# Display.net
KiCad netlist of a schematic drawn in EAGLE
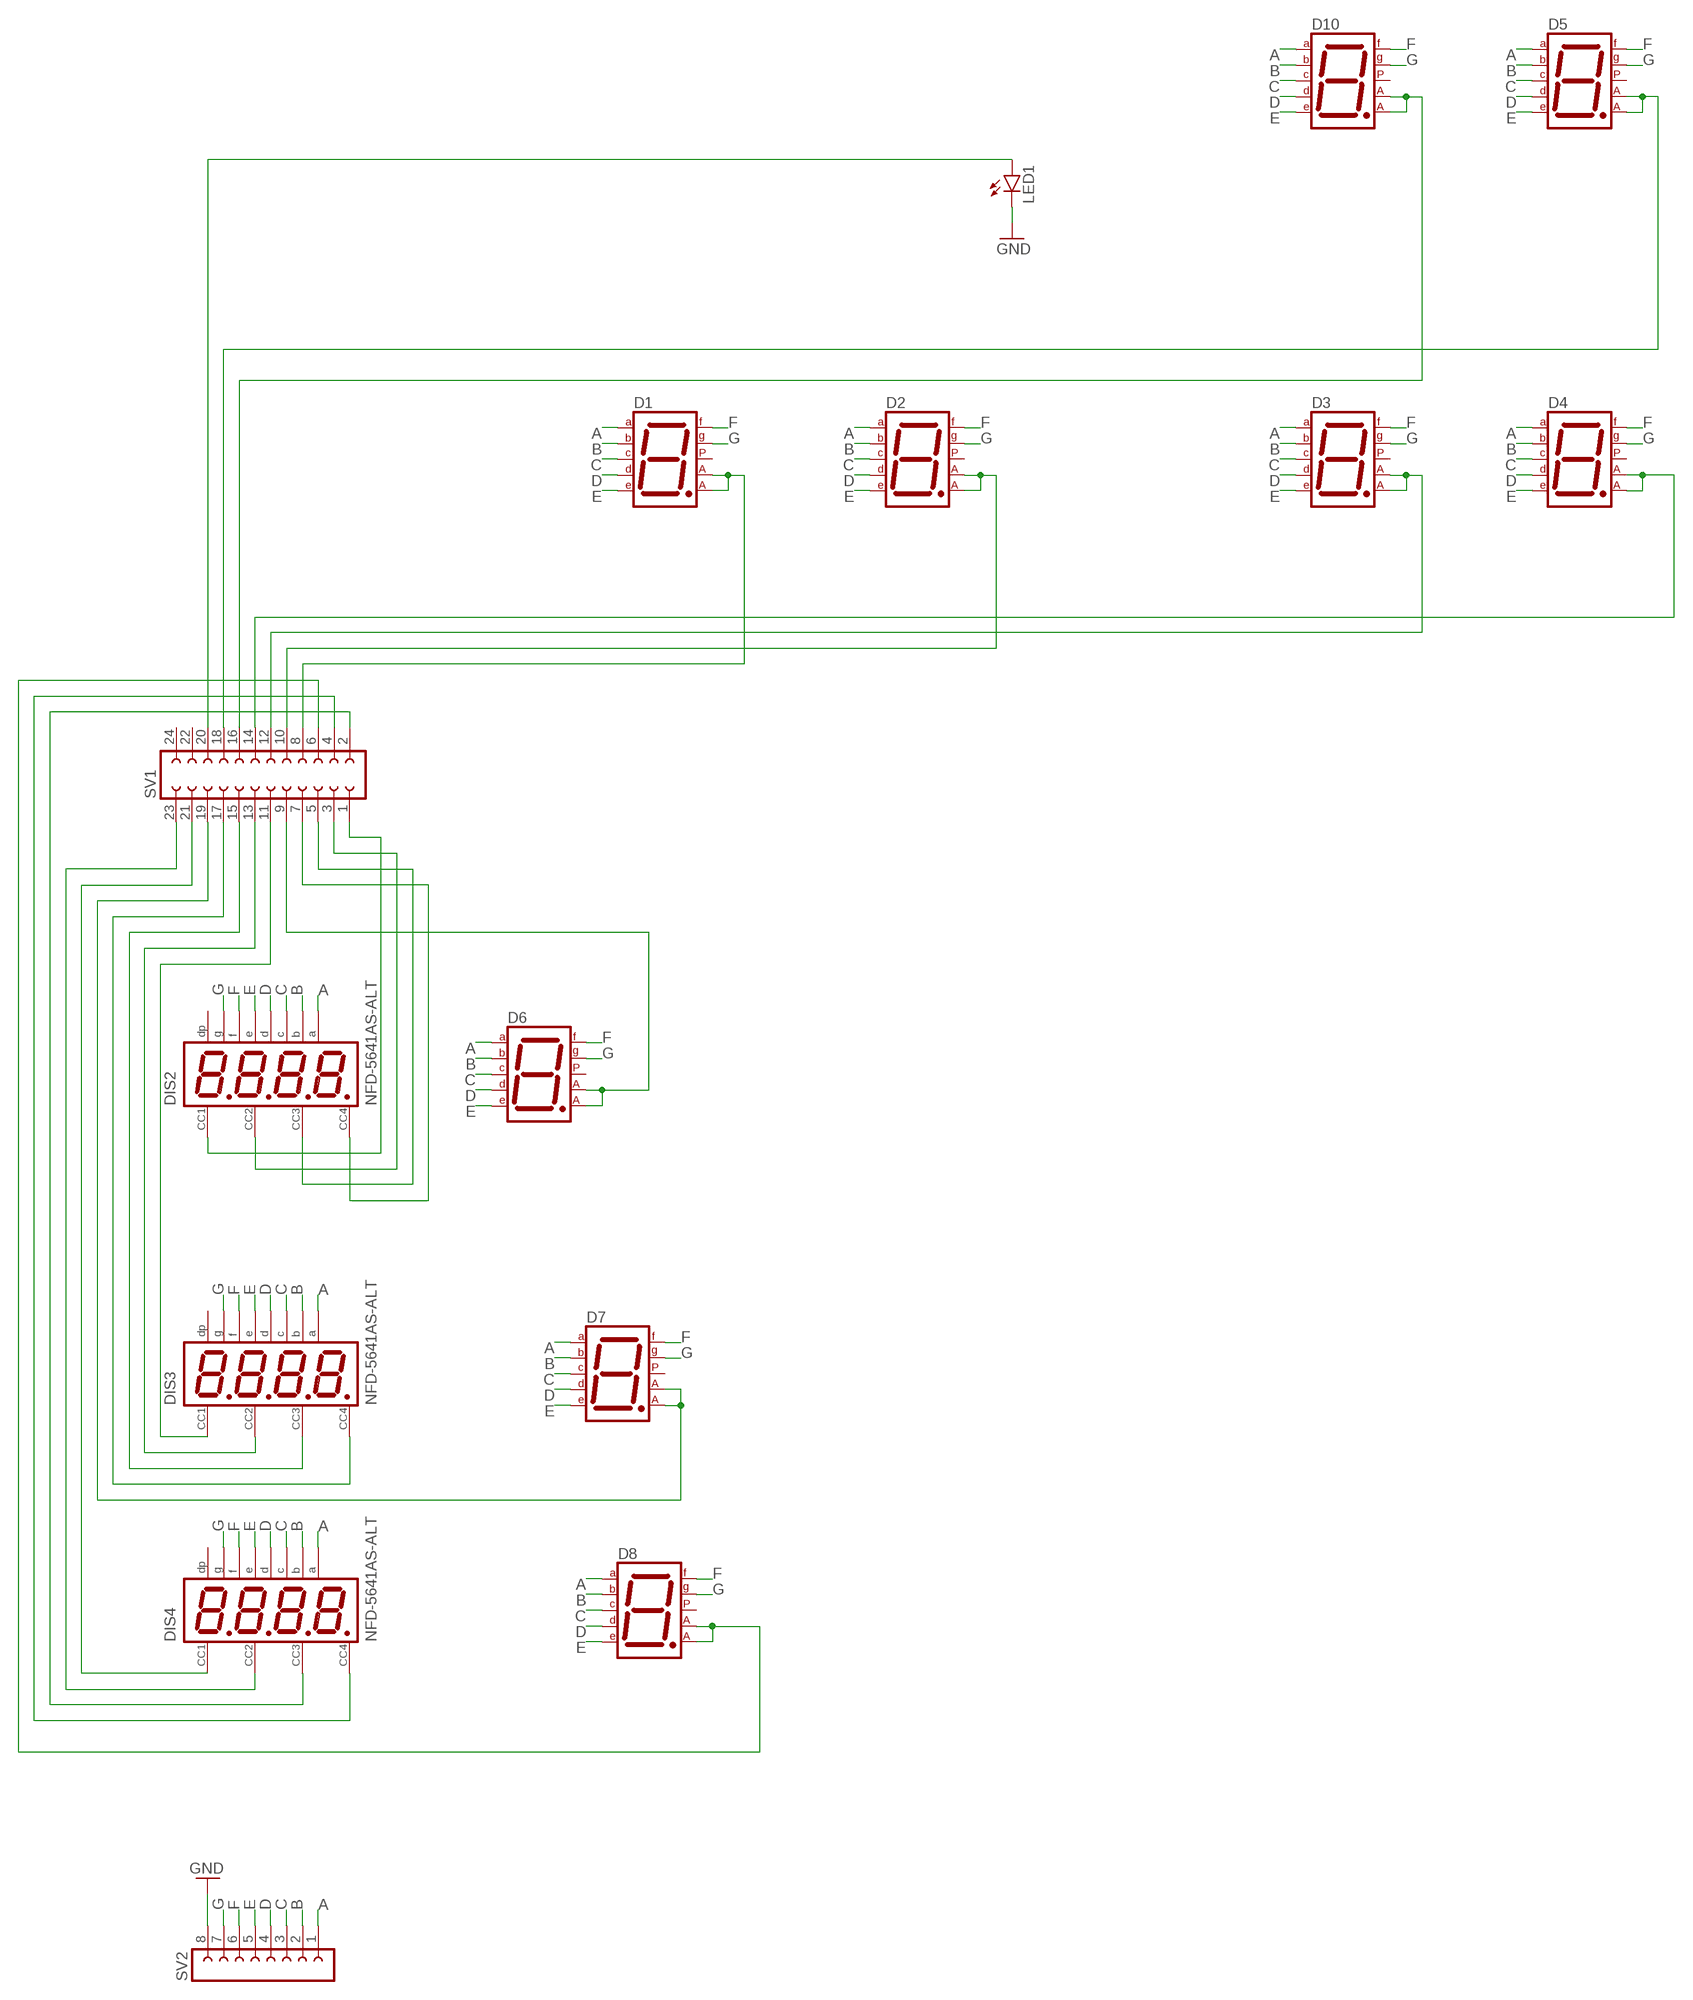
[diagram p0: schematic, sheet 1]

(export (version "E")
  (design (tool "Eeschema 10.0.6"))
  (components
    (comp (ref "D1")
      (value "7SEG-CA")
      (footprint "eagle-import:7SEG-13")
      (libsource (lib "eagle-import") (part "7SEG-CA"))
    )
    (comp (ref "D2")
      (value "7SEG-CA")
      (footprint "eagle-import:7SEG-13")
      (libsource (lib "eagle-import") (part "7SEG-CA"))
    )
    (comp (ref "D3")
      (value "7SEG-CA")
      (footprint "eagle-import:7SEG-13")
      (libsource (lib "eagle-import") (part "7SEG-CA"))
    )
    (comp (ref "D4")
      (value "7SEG-CA")
      (footprint "eagle-import:7SEG-13")
      (libsource (lib "eagle-import") (part "7SEG-CA"))
    )
    (comp (ref "D5")
      (value "7SEG-CA")
      (footprint "eagle-import:7SEG-13")
      (libsource (lib "eagle-import") (part "7SEG-CA"))
    )
    (comp (ref "D6")
      (value "7SEG-CA")
      (footprint "eagle-import:7SEG-13")
      (libsource (lib "eagle-import") (part "7SEG-CA"))
    )
    (comp (ref "D7")
      (value "7SEG-CA")
      (footprint "eagle-import:7SEG-13")
      (libsource (lib "eagle-import") (part "7SEG-CA"))
    )
    (comp (ref "D8")
      (value "7SEG-CA")
      (footprint "eagle-import:7SEG-13")
      (libsource (lib "eagle-import") (part "7SEG-CA"))
    )
    (comp (ref "D10")
      (value "7SEG-CA")
      (footprint "eagle-import:7SEG-13")
      (libsource (lib "eagle-import") (part "7SEG-CA"))
    )
    (comp (ref "DIS2")
      (value "NFD-5641AS-ALT")
      (footprint "eagle-import:NFD-5641")
      (libsource (lib "eagle-import") (part "NFD-5641AS-ALT"))
    )
    (comp (ref "DIS3")
      (value "NFD-5641AS-ALT")
      (footprint "eagle-import:NFD-5641")
      (libsource (lib "eagle-import") (part "NFD-5641AS-ALT"))
    )
    (comp (ref "DIS4")
      (value "NFD-5641AS-ALT")
      (footprint "eagle-import:NFD-5641")
      (libsource (lib "eagle-import") (part "NFD-5641AS-ALT"))
    )
    (comp (ref "LED1")
      (value "LED5MM")
      (footprint "eagle-import:LED5MM")
      (libsource (lib "eagle-import") (part "LED5MM"))
    )
    (comp (ref "SV1")
      (value "FE12-2")
      (footprint "eagle-import:FE12-2")
      (libsource (lib "eagle-import") (part "FE12-2"))
    )
    (comp (ref "SV2")
      (value "FE08-1")
      (footprint "eagle-import:FE08")
      (libsource (lib "eagle-import") (part "FE08-1"))
    )
  )
  (nets
    (net (code "1") (name "/A") (class "Default")
      (node (ref "D1") (pin "7") (pinfunction "A_7") (pintype "passive"))
      (node (ref "D10") (pin "7") (pinfunction "A_7") (pintype "passive"))
      (node (ref "D2") (pin "7") (pinfunction "A_7") (pintype "passive"))
      (node (ref "D3") (pin "7") (pinfunction "A_7") (pintype "passive"))
      (node (ref "D4") (pin "7") (pinfunction "A_7") (pintype "passive"))
      (node (ref "D5") (pin "7") (pinfunction "A_7") (pintype "passive"))
      (node (ref "D6") (pin "7") (pinfunction "A_7") (pintype "passive"))
      (node (ref "D7") (pin "7") (pinfunction "A_7") (pintype "passive"))
      (node (ref "D8") (pin "7") (pinfunction "A_7") (pintype "passive"))
      (node (ref "DIS2") (pin "P$11") (pinfunction "P$11_P$11") (pintype "bidirectional"))
      (node (ref "DIS3") (pin "P$11") (pinfunction "P$11_P$11") (pintype "bidirectional"))
      (node (ref "DIS4") (pin "P$11") (pinfunction "P$11_P$11") (pintype "bidirectional"))
      (node (ref "SV2") (pin "1") (pinfunction "1_1") (pintype "passive"))
    )
    (net (code "2") (name "/B") (class "Default")
      (node (ref "D1") (pin "6") (pinfunction "B_6") (pintype "passive"))
      (node (ref "D10") (pin "6") (pinfunction "B_6") (pintype "passive"))
      (node (ref "D2") (pin "6") (pinfunction "B_6") (pintype "passive"))
      (node (ref "D3") (pin "6") (pinfunction "B_6") (pintype "passive"))
      (node (ref "D4") (pin "6") (pinfunction "B_6") (pintype "passive"))
      (node (ref "D5") (pin "6") (pinfunction "B_6") (pintype "passive"))
      (node (ref "D6") (pin "6") (pinfunction "B_6") (pintype "passive"))
      (node (ref "D7") (pin "6") (pinfunction "B_6") (pintype "passive"))
      (node (ref "D8") (pin "6") (pinfunction "B_6") (pintype "passive"))
      (node (ref "DIS2") (pin "P$7") (pinfunction "P$7_P$7") (pintype "bidirectional"))
      (node (ref "DIS3") (pin "P$7") (pinfunction "P$7_P$7") (pintype "bidirectional"))
      (node (ref "DIS4") (pin "P$7") (pinfunction "P$7_P$7") (pintype "bidirectional"))
      (node (ref "SV2") (pin "2") (pinfunction "2_2") (pintype "passive"))
    )
    (net (code "3") (name "/C") (class "Default")
      (node (ref "D1") (pin "4") (pinfunction "C_4") (pintype "passive"))
      (node (ref "D10") (pin "4") (pinfunction "C_4") (pintype "passive"))
      (node (ref "D2") (pin "4") (pinfunction "C_4") (pintype "passive"))
      (node (ref "D3") (pin "4") (pinfunction "C_4") (pintype "passive"))
      (node (ref "D4") (pin "4") (pinfunction "C_4") (pintype "passive"))
      (node (ref "D5") (pin "4") (pinfunction "C_4") (pintype "passive"))
      (node (ref "D6") (pin "4") (pinfunction "C_4") (pintype "passive"))
      (node (ref "D7") (pin "4") (pinfunction "C_4") (pintype "passive"))
      (node (ref "D8") (pin "4") (pinfunction "C_4") (pintype "passive"))
      (node (ref "DIS2") (pin "P$4") (pinfunction "P$4_P$4") (pintype "bidirectional"))
      (node (ref "DIS3") (pin "P$4") (pinfunction "P$4_P$4") (pintype "bidirectional"))
      (node (ref "DIS4") (pin "P$4") (pinfunction "P$4_P$4") (pintype "bidirectional"))
      (node (ref "SV2") (pin "3") (pinfunction "3_3") (pintype "passive"))
    )
    (net (code "4") (name "/D") (class "Default")
      (node (ref "D1") (pin "2") (pinfunction "D_2") (pintype "passive"))
      (node (ref "D10") (pin "2") (pinfunction "D_2") (pintype "passive"))
      (node (ref "D2") (pin "2") (pinfunction "D_2") (pintype "passive"))
      (node (ref "D3") (pin "2") (pinfunction "D_2") (pintype "passive"))
      (node (ref "D4") (pin "2") (pinfunction "D_2") (pintype "passive"))
      (node (ref "D5") (pin "2") (pinfunction "D_2") (pintype "passive"))
      (node (ref "D6") (pin "2") (pinfunction "D_2") (pintype "passive"))
      (node (ref "D7") (pin "2") (pinfunction "D_2") (pintype "passive"))
      (node (ref "D8") (pin "2") (pinfunction "D_2") (pintype "passive"))
      (node (ref "DIS2") (pin "P$2") (pinfunction "P$2_P$2") (pintype "bidirectional"))
      (node (ref "DIS3") (pin "P$2") (pinfunction "P$2_P$2") (pintype "bidirectional"))
      (node (ref "DIS4") (pin "P$2") (pinfunction "P$2_P$2") (pintype "bidirectional"))
      (node (ref "SV2") (pin "4") (pinfunction "4_4") (pintype "passive"))
    )
    (net (code "5") (name "/E") (class "Default")
      (node (ref "D1") (pin "1") (pinfunction "E_1") (pintype "passive"))
      (node (ref "D10") (pin "1") (pinfunction "E_1") (pintype "passive"))
      (node (ref "D2") (pin "1") (pinfunction "E_1") (pintype "passive"))
      (node (ref "D3") (pin "1") (pinfunction "E_1") (pintype "passive"))
      (node (ref "D4") (pin "1") (pinfunction "E_1") (pintype "passive"))
      (node (ref "D5") (pin "1") (pinfunction "E_1") (pintype "passive"))
      (node (ref "D6") (pin "1") (pinfunction "E_1") (pintype "passive"))
      (node (ref "D7") (pin "1") (pinfunction "E_1") (pintype "passive"))
      (node (ref "D8") (pin "1") (pinfunction "E_1") (pintype "passive"))
      (node (ref "DIS2") (pin "P$1") (pinfunction "P$1_P$1") (pintype "bidirectional"))
      (node (ref "DIS3") (pin "P$1") (pinfunction "P$1_P$1") (pintype "bidirectional"))
      (node (ref "DIS4") (pin "P$1") (pinfunction "P$1_P$1") (pintype "bidirectional"))
      (node (ref "SV2") (pin "5") (pinfunction "5_5") (pintype "passive"))
    )
    (net (code "6") (name "/F") (class "Default")
      (node (ref "D1") (pin "9") (pinfunction "F_9") (pintype "passive"))
      (node (ref "D10") (pin "9") (pinfunction "F_9") (pintype "passive"))
      (node (ref "D2") (pin "9") (pinfunction "F_9") (pintype "passive"))
      (node (ref "D3") (pin "9") (pinfunction "F_9") (pintype "passive"))
      (node (ref "D4") (pin "9") (pinfunction "F_9") (pintype "passive"))
      (node (ref "D5") (pin "9") (pinfunction "F_9") (pintype "passive"))
      (node (ref "D6") (pin "9") (pinfunction "F_9") (pintype "passive"))
      (node (ref "D7") (pin "9") (pinfunction "F_9") (pintype "passive"))
      (node (ref "D8") (pin "9") (pinfunction "F_9") (pintype "passive"))
      (node (ref "DIS2") (pin "P$10") (pinfunction "P$10_P$10") (pintype "bidirectional"))
      (node (ref "DIS3") (pin "P$10") (pinfunction "P$10_P$10") (pintype "bidirectional"))
      (node (ref "DIS4") (pin "P$10") (pinfunction "P$10_P$10") (pintype "bidirectional"))
      (node (ref "SV2") (pin "6") (pinfunction "6_6") (pintype "passive"))
    )
    (net (code "7") (name "/G") (class "Default")
      (node (ref "D1") (pin "10") (pinfunction "G_10") (pintype "passive"))
      (node (ref "D10") (pin "10") (pinfunction "G_10") (pintype "passive"))
      (node (ref "D2") (pin "10") (pinfunction "G_10") (pintype "passive"))
      (node (ref "D3") (pin "10") (pinfunction "G_10") (pintype "passive"))
      (node (ref "D4") (pin "10") (pinfunction "G_10") (pintype "passive"))
      (node (ref "D5") (pin "10") (pinfunction "G_10") (pintype "passive"))
      (node (ref "D6") (pin "10") (pinfunction "G_10") (pintype "passive"))
      (node (ref "D7") (pin "10") (pinfunction "G_10") (pintype "passive"))
      (node (ref "D8") (pin "10") (pinfunction "G_10") (pintype "passive"))
      (node (ref "DIS2") (pin "P$5") (pinfunction "P$5_P$5") (pintype "bidirectional"))
      (node (ref "DIS3") (pin "P$5") (pinfunction "P$5_P$5") (pintype "bidirectional"))
      (node (ref "DIS4") (pin "P$5") (pinfunction "P$5_P$5") (pintype "bidirectional"))
      (node (ref "SV2") (pin "7") (pinfunction "7_7") (pintype "passive"))
    )
    (net (code "8") (name "GND") (class "Default")
      (node (ref "LED1") (pin "K") (pinfunction "C_K") (pintype "passive"))
      (node (ref "SV2") (pin "8") (pinfunction "8_8") (pintype "passive"))
    )
    (net (code "9") (name "Net-(D1-CA1)") (class "Default")
      (node (ref "D1") (pin "3") (pinfunction "CA1_3") (pintype "passive"))
      (node (ref "D1") (pin "8") (pinfunction "CA2_8") (pintype "passive"))
      (node (ref "SV1") (pin "8") (pinfunction "8_8") (pintype "passive"))
    )
    (net (code "10") (name "Net-(D2-CA1)") (class "Default")
      (node (ref "D2") (pin "3") (pinfunction "CA1_3") (pintype "passive"))
      (node (ref "D2") (pin "8") (pinfunction "CA2_8") (pintype "passive"))
      (node (ref "SV1") (pin "10") (pinfunction "10_10") (pintype "passive"))
    )
    (net (code "11") (name "Net-(D3-CA1)") (class "Default")
      (node (ref "D3") (pin "3") (pinfunction "CA1_3") (pintype "passive"))
      (node (ref "D3") (pin "8") (pinfunction "CA2_8") (pintype "passive"))
      (node (ref "SV1") (pin "12") (pinfunction "12_12") (pintype "passive"))
    )
    (net (code "12") (name "Net-(D4-CA1)") (class "Default")
      (node (ref "D4") (pin "3") (pinfunction "CA1_3") (pintype "passive"))
      (node (ref "D4") (pin "8") (pinfunction "CA2_8") (pintype "passive"))
      (node (ref "SV1") (pin "14") (pinfunction "14_14") (pintype "passive"))
    )
    (net (code "13") (name "Net-(D5-CA1)") (class "Default")
      (node (ref "D5") (pin "3") (pinfunction "CA1_3") (pintype "passive"))
      (node (ref "D5") (pin "8") (pinfunction "CA2_8") (pintype "passive"))
      (node (ref "SV1") (pin "18") (pinfunction "18_18") (pintype "passive"))
    )
    (net (code "14") (name "Net-(D6-CA1)") (class "Default")
      (node (ref "D6") (pin "3") (pinfunction "CA1_3") (pintype "passive"))
      (node (ref "D6") (pin "8") (pinfunction "CA2_8") (pintype "passive"))
      (node (ref "SV1") (pin "9") (pinfunction "9_9") (pintype "passive"))
    )
    (net (code "15") (name "Net-(D7-CA1)") (class "Default")
      (node (ref "D7") (pin "3") (pinfunction "CA1_3") (pintype "passive"))
      (node (ref "D7") (pin "8") (pinfunction "CA2_8") (pintype "passive"))
      (node (ref "SV1") (pin "19") (pinfunction "19_19") (pintype "passive"))
    )
    (net (code "16") (name "Net-(D8-CA1)") (class "Default")
      (node (ref "D8") (pin "3") (pinfunction "CA1_3") (pintype "passive"))
      (node (ref "D8") (pin "8") (pinfunction "CA2_8") (pintype "passive"))
      (node (ref "SV1") (pin "6") (pinfunction "6_6") (pintype "passive"))
    )
    (net (code "17") (name "Net-(D10-CA1)") (class "Default")
      (node (ref "D10") (pin "3") (pinfunction "CA1_3") (pintype "passive"))
      (node (ref "D10") (pin "8") (pinfunction "CA2_8") (pintype "passive"))
      (node (ref "SV1") (pin "16") (pinfunction "16_16") (pintype "passive"))
    )
    (net (code "18") (name "Net-(DIS2-PadP$6)") (class "Default")
      (node (ref "DIS2") (pin "P$6") (pinfunction "P$6_P$6") (pintype "bidirectional"))
      (node (ref "SV1") (pin "7") (pinfunction "7_7") (pintype "passive"))
    )
    (net (code "19") (name "Net-(DIS2-PadP$8)") (class "Default")
      (node (ref "DIS2") (pin "P$8") (pinfunction "P$8_P$8") (pintype "bidirectional"))
      (node (ref "SV1") (pin "5") (pinfunction "5_5") (pintype "passive"))
    )
    (net (code "20") (name "Net-(DIS2-PadP$9)") (class "Default")
      (node (ref "DIS2") (pin "P$9") (pinfunction "P$9_P$9") (pintype "bidirectional"))
      (node (ref "SV1") (pin "3") (pinfunction "3_3") (pintype "passive"))
    )
    (net (code "21") (name "Net-(DIS2-PadP$12)") (class "Default")
      (node (ref "DIS2") (pin "P$12") (pinfunction "P$12_P$12") (pintype "bidirectional"))
      (node (ref "SV1") (pin "1") (pinfunction "1_1") (pintype "passive"))
    )
    (net (code "22") (name "Net-(DIS3-PadP$6)") (class "Default")
      (node (ref "DIS3") (pin "P$6") (pinfunction "P$6_P$6") (pintype "bidirectional"))
      (node (ref "SV1") (pin "17") (pinfunction "17_17") (pintype "passive"))
    )
    (net (code "23") (name "Net-(DIS3-PadP$8)") (class "Default")
      (node (ref "DIS3") (pin "P$8") (pinfunction "P$8_P$8") (pintype "bidirectional"))
      (node (ref "SV1") (pin "15") (pinfunction "15_15") (pintype "passive"))
    )
    (net (code "24") (name "Net-(DIS3-PadP$9)") (class "Default")
      (node (ref "DIS3") (pin "P$9") (pinfunction "P$9_P$9") (pintype "bidirectional"))
      (node (ref "SV1") (pin "13") (pinfunction "13_13") (pintype "passive"))
    )
    (net (code "25") (name "Net-(DIS3-PadP$12)") (class "Default")
      (node (ref "DIS3") (pin "P$12") (pinfunction "P$12_P$12") (pintype "bidirectional"))
      (node (ref "SV1") (pin "11") (pinfunction "11_11") (pintype "passive"))
    )
    (net (code "26") (name "Net-(DIS4-PadP$6)") (class "Default")
      (node (ref "DIS4") (pin "P$6") (pinfunction "P$6_P$6") (pintype "bidirectional"))
      (node (ref "SV1") (pin "4") (pinfunction "4_4") (pintype "passive"))
    )
    (net (code "27") (name "Net-(DIS4-PadP$8)") (class "Default")
      (node (ref "DIS4") (pin "P$8") (pinfunction "P$8_P$8") (pintype "bidirectional"))
      (node (ref "SV1") (pin "2") (pinfunction "2_2") (pintype "passive"))
    )
    (net (code "28") (name "Net-(DIS4-PadP$9)") (class "Default")
      (node (ref "DIS4") (pin "P$9") (pinfunction "P$9_P$9") (pintype "bidirectional"))
      (node (ref "SV1") (pin "23") (pinfunction "23_23") (pintype "passive"))
    )
    (net (code "29") (name "Net-(DIS4-PadP$12)") (class "Default")
      (node (ref "DIS4") (pin "P$12") (pinfunction "P$12_P$12") (pintype "bidirectional"))
      (node (ref "SV1") (pin "21") (pinfunction "21_21") (pintype "passive"))
    )
    (net (code "30") (name "Net-(LED1-PadA)") (class "Default")
      (node (ref "LED1") (pin "A") (pinfunction "A_A") (pintype "passive"))
      (node (ref "SV1") (pin "20") (pinfunction "20_20") (pintype "passive"))
    )
    (net (code "31") (name "unconnected-(D1-DP-Pad5)") (class "Default")
      (node (ref "D1") (pin "5") (pinfunction "DP_5") (pintype "passive"))
    )
    (net (code "32") (name "unconnected-(D2-DP-Pad5)") (class "Default")
      (node (ref "D2") (pin "5") (pinfunction "DP_5") (pintype "passive"))
    )
    (net (code "33") (name "unconnected-(D3-DP-Pad5)") (class "Default")
      (node (ref "D3") (pin "5") (pinfunction "DP_5") (pintype "passive"))
    )
    (net (code "34") (name "unconnected-(D4-DP-Pad5)") (class "Default")
      (node (ref "D4") (pin "5") (pinfunction "DP_5") (pintype "passive"))
    )
    (net (code "35") (name "unconnected-(D5-DP-Pad5)") (class "Default")
      (node (ref "D5") (pin "5") (pinfunction "DP_5") (pintype "passive"))
    )
    (net (code "36") (name "unconnected-(D6-DP-Pad5)") (class "Default")
      (node (ref "D6") (pin "5") (pinfunction "DP_5") (pintype "passive"))
    )
    (net (code "37") (name "unconnected-(D7-DP-Pad5)") (class "Default")
      (node (ref "D7") (pin "5") (pinfunction "DP_5") (pintype "passive"))
    )
    (net (code "38") (name "unconnected-(D8-DP-Pad5)") (class "Default")
      (node (ref "D8") (pin "5") (pinfunction "DP_5") (pintype "passive"))
    )
    (net (code "39") (name "unconnected-(D10-DP-Pad5)") (class "Default")
      (node (ref "D10") (pin "5") (pinfunction "DP_5") (pintype "passive"))
    )
    (net (code "40") (name "unconnected-(DIS2-PadP$3)") (class "Default")
      (node (ref "DIS2") (pin "P$3") (pinfunction "P$3_P$3") (pintype "bidirectional"))
    )
    (net (code "41") (name "unconnected-(DIS3-PadP$3)") (class "Default")
      (node (ref "DIS3") (pin "P$3") (pinfunction "P$3_P$3") (pintype "bidirectional"))
    )
    (net (code "42") (name "unconnected-(DIS4-PadP$3)") (class "Default")
      (node (ref "DIS4") (pin "P$3") (pinfunction "P$3_P$3") (pintype "bidirectional"))
    )
    (net (code "43") (name "unconnected-(SV1-Pad22)") (class "Default")
      (node (ref "SV1") (pin "22") (pinfunction "22_22") (pintype "passive"))
    )
    (net (code "44") (name "unconnected-(SV1-Pad24)") (class "Default")
      (node (ref "SV1") (pin "24") (pinfunction "24_24") (pintype "passive"))
    )
  )
)
